# BarGraph.net
KiCad netlist of a schematic drawn in EAGLE
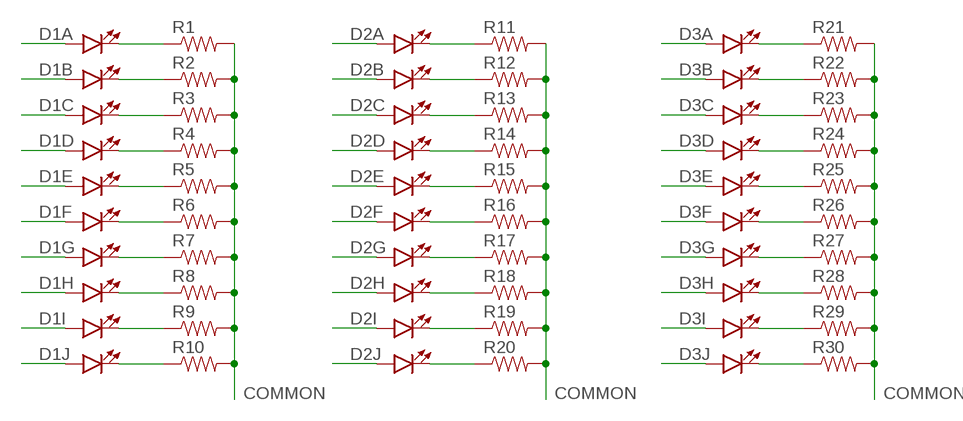
[diagram p0: schematic, sheet 1]

(export (version "E")
  (design (tool "Eeschema 10.0.6"))
  (components
    (comp (ref "D1")
      (value "LED_BARGRAPH_10")
      (footprint "eagle-import:LED_BARGAPH_10")
      (libsource (lib "eagle-import") (part "LED_BARGRAPH_10"))
    )
    (comp (ref "D2")
      (value "LED_BARGRAPH_10")
      (footprint "eagle-import:LED_BARGAPH_10")
      (libsource (lib "eagle-import") (part "LED_BARGRAPH_10"))
    )
    (comp (ref "D3")
      (value "LED_BARGRAPH_10")
      (footprint "eagle-import:LED_BARGAPH_10")
      (libsource (lib "eagle-import") (part "LED_BARGRAPH_10"))
    )
    (comp (ref "R1")
      (value "RESISTORPTH-1/4W")
      (footprint "eagle-import:AXIAL-0.4")
      (libsource (lib "eagle-import") (part "RESISTORPTH-1/4W"))
    )
    (comp (ref "R2")
      (value "RESISTORPTH-1/4W")
      (footprint "eagle-import:AXIAL-0.4")
      (libsource (lib "eagle-import") (part "RESISTORPTH-1/4W"))
    )
    (comp (ref "R3")
      (value "RESISTORPTH-1/4W")
      (footprint "eagle-import:AXIAL-0.4")
      (libsource (lib "eagle-import") (part "RESISTORPTH-1/4W"))
    )
    (comp (ref "R4")
      (value "RESISTORPTH-1/4W")
      (footprint "eagle-import:AXIAL-0.4")
      (libsource (lib "eagle-import") (part "RESISTORPTH-1/4W"))
    )
    (comp (ref "R5")
      (value "RESISTORPTH-1/4W")
      (footprint "eagle-import:AXIAL-0.4")
      (libsource (lib "eagle-import") (part "RESISTORPTH-1/4W"))
    )
    (comp (ref "R6")
      (value "RESISTORPTH-1/4W")
      (footprint "eagle-import:AXIAL-0.4")
      (libsource (lib "eagle-import") (part "RESISTORPTH-1/4W"))
    )
    (comp (ref "R7")
      (value "RESISTORPTH-1/4W")
      (footprint "eagle-import:AXIAL-0.4")
      (libsource (lib "eagle-import") (part "RESISTORPTH-1/4W"))
    )
    (comp (ref "R8")
      (value "RESISTORPTH-1/4W")
      (footprint "eagle-import:AXIAL-0.4")
      (libsource (lib "eagle-import") (part "RESISTORPTH-1/4W"))
    )
    (comp (ref "R9")
      (value "RESISTORPTH-1/4W")
      (footprint "eagle-import:AXIAL-0.4")
      (libsource (lib "eagle-import") (part "RESISTORPTH-1/4W"))
    )
    (comp (ref "R10")
      (value "RESISTORPTH-1/4W")
      (footprint "eagle-import:AXIAL-0.4")
      (libsource (lib "eagle-import") (part "RESISTORPTH-1/4W"))
    )
    (comp (ref "R11")
      (value "RESISTORPTH-1/4W")
      (footprint "eagle-import:AXIAL-0.4")
      (libsource (lib "eagle-import") (part "RESISTORPTH-1/4W"))
    )
    (comp (ref "R12")
      (value "RESISTORPTH-1/4W")
      (footprint "eagle-import:AXIAL-0.4")
      (libsource (lib "eagle-import") (part "RESISTORPTH-1/4W"))
    )
    (comp (ref "R13")
      (value "RESISTORPTH-1/4W")
      (footprint "eagle-import:AXIAL-0.4")
      (libsource (lib "eagle-import") (part "RESISTORPTH-1/4W"))
    )
    (comp (ref "R14")
      (value "RESISTORPTH-1/4W")
      (footprint "eagle-import:AXIAL-0.4")
      (libsource (lib "eagle-import") (part "RESISTORPTH-1/4W"))
    )
    (comp (ref "R15")
      (value "RESISTORPTH-1/4W")
      (footprint "eagle-import:AXIAL-0.4")
      (libsource (lib "eagle-import") (part "RESISTORPTH-1/4W"))
    )
    (comp (ref "R16")
      (value "RESISTORPTH-1/4W")
      (footprint "eagle-import:AXIAL-0.4")
      (libsource (lib "eagle-import") (part "RESISTORPTH-1/4W"))
    )
    (comp (ref "R17")
      (value "RESISTORPTH-1/4W")
      (footprint "eagle-import:AXIAL-0.4")
      (libsource (lib "eagle-import") (part "RESISTORPTH-1/4W"))
    )
    (comp (ref "R18")
      (value "RESISTORPTH-1/4W")
      (footprint "eagle-import:AXIAL-0.4")
      (libsource (lib "eagle-import") (part "RESISTORPTH-1/4W"))
    )
    (comp (ref "R19")
      (value "RESISTORPTH-1/4W")
      (footprint "eagle-import:AXIAL-0.4")
      (libsource (lib "eagle-import") (part "RESISTORPTH-1/4W"))
    )
    (comp (ref "R20")
      (value "RESISTORPTH-1/4W")
      (footprint "eagle-import:AXIAL-0.4")
      (libsource (lib "eagle-import") (part "RESISTORPTH-1/4W"))
    )
    (comp (ref "R21")
      (value "RESISTORPTH-1/4W")
      (footprint "eagle-import:AXIAL-0.4")
      (libsource (lib "eagle-import") (part "RESISTORPTH-1/4W"))
    )
    (comp (ref "R22")
      (value "RESISTORPTH-1/4W")
      (footprint "eagle-import:AXIAL-0.4")
      (libsource (lib "eagle-import") (part "RESISTORPTH-1/4W"))
    )
    (comp (ref "R23")
      (value "RESISTORPTH-1/4W")
      (footprint "eagle-import:AXIAL-0.4")
      (libsource (lib "eagle-import") (part "RESISTORPTH-1/4W"))
    )
    (comp (ref "R24")
      (value "RESISTORPTH-1/4W")
      (footprint "eagle-import:AXIAL-0.4")
      (libsource (lib "eagle-import") (part "RESISTORPTH-1/4W"))
    )
    (comp (ref "R25")
      (value "RESISTORPTH-1/4W")
      (footprint "eagle-import:AXIAL-0.4")
      (libsource (lib "eagle-import") (part "RESISTORPTH-1/4W"))
    )
    (comp (ref "R26")
      (value "RESISTORPTH-1/4W")
      (footprint "eagle-import:AXIAL-0.4")
      (libsource (lib "eagle-import") (part "RESISTORPTH-1/4W"))
    )
    (comp (ref "R27")
      (value "RESISTORPTH-1/4W")
      (footprint "eagle-import:AXIAL-0.4")
      (libsource (lib "eagle-import") (part "RESISTORPTH-1/4W"))
    )
    (comp (ref "R28")
      (value "RESISTORPTH-1/4W")
      (footprint "eagle-import:AXIAL-0.4")
      (libsource (lib "eagle-import") (part "RESISTORPTH-1/4W"))
    )
    (comp (ref "R29")
      (value "RESISTORPTH-1/4W")
      (footprint "eagle-import:AXIAL-0.4")
      (libsource (lib "eagle-import") (part "RESISTORPTH-1/4W"))
    )
    (comp (ref "R30")
      (value "RESISTORPTH-1/4W")
      (footprint "eagle-import:AXIAL-0.4")
      (libsource (lib "eagle-import") (part "RESISTORPTH-1/4W"))
    )
  )
  (nets
    (net (code "1") (name "/COMMON") (class "Default")
      (node (ref "R1") (pin "P$2") (pinfunction "2_P$2") (pintype "passive"))
      (node (ref "R10") (pin "P$2") (pinfunction "2_P$2") (pintype "passive"))
      (node (ref "R11") (pin "P$2") (pinfunction "2_P$2") (pintype "passive"))
      (node (ref "R12") (pin "P$2") (pinfunction "2_P$2") (pintype "passive"))
      (node (ref "R13") (pin "P$2") (pinfunction "2_P$2") (pintype "passive"))
      (node (ref "R14") (pin "P$2") (pinfunction "2_P$2") (pintype "passive"))
      (node (ref "R15") (pin "P$2") (pinfunction "2_P$2") (pintype "passive"))
      (node (ref "R16") (pin "P$2") (pinfunction "2_P$2") (pintype "passive"))
      (node (ref "R17") (pin "P$2") (pinfunction "2_P$2") (pintype "passive"))
      (node (ref "R18") (pin "P$2") (pinfunction "2_P$2") (pintype "passive"))
      (node (ref "R19") (pin "P$2") (pinfunction "2_P$2") (pintype "passive"))
      (node (ref "R2") (pin "P$2") (pinfunction "2_P$2") (pintype "passive"))
      (node (ref "R20") (pin "P$2") (pinfunction "2_P$2") (pintype "passive"))
      (node (ref "R21") (pin "P$2") (pinfunction "2_P$2") (pintype "passive"))
      (node (ref "R22") (pin "P$2") (pinfunction "2_P$2") (pintype "passive"))
      (node (ref "R23") (pin "P$2") (pinfunction "2_P$2") (pintype "passive"))
      (node (ref "R24") (pin "P$2") (pinfunction "2_P$2") (pintype "passive"))
      (node (ref "R25") (pin "P$2") (pinfunction "2_P$2") (pintype "passive"))
      (node (ref "R26") (pin "P$2") (pinfunction "2_P$2") (pintype "passive"))
      (node (ref "R27") (pin "P$2") (pinfunction "2_P$2") (pintype "passive"))
      (node (ref "R28") (pin "P$2") (pinfunction "2_P$2") (pintype "passive"))
      (node (ref "R29") (pin "P$2") (pinfunction "2_P$2") (pintype "passive"))
      (node (ref "R3") (pin "P$2") (pinfunction "2_P$2") (pintype "passive"))
      (node (ref "R30") (pin "P$2") (pinfunction "2_P$2") (pintype "passive"))
      (node (ref "R4") (pin "P$2") (pinfunction "2_P$2") (pintype "passive"))
      (node (ref "R5") (pin "P$2") (pinfunction "2_P$2") (pintype "passive"))
      (node (ref "R6") (pin "P$2") (pinfunction "2_P$2") (pintype "passive"))
      (node (ref "R7") (pin "P$2") (pinfunction "2_P$2") (pintype "passive"))
      (node (ref "R8") (pin "P$2") (pinfunction "2_P$2") (pintype "passive"))
      (node (ref "R9") (pin "P$2") (pinfunction "2_P$2") (pintype "passive"))
    )
    (net (code "2") (name "Net-(D1A-C)") (class "Default")
      (node (ref "D1") (pin "20") (pinfunction "C_20") (pintype "passive"))
      (node (ref "R1") (pin "P$1") (pinfunction "1_P$1") (pintype "passive"))
    )
    (net (code "3") (name "Net-(D1B-C)") (class "Default")
      (node (ref "D1") (pin "19") (pinfunction "C_19") (pintype "passive"))
      (node (ref "R2") (pin "P$1") (pinfunction "1_P$1") (pintype "passive"))
    )
    (net (code "4") (name "Net-(D1C-C)") (class "Default")
      (node (ref "D1") (pin "18") (pinfunction "C_18") (pintype "passive"))
      (node (ref "R3") (pin "P$1") (pinfunction "1_P$1") (pintype "passive"))
    )
    (net (code "5") (name "Net-(D1D-C)") (class "Default")
      (node (ref "D1") (pin "17") (pinfunction "C_17") (pintype "passive"))
      (node (ref "R4") (pin "P$1") (pinfunction "1_P$1") (pintype "passive"))
    )
    (net (code "6") (name "Net-(D1E-C)") (class "Default")
      (node (ref "D1") (pin "16") (pinfunction "C_16") (pintype "passive"))
      (node (ref "R5") (pin "P$1") (pinfunction "1_P$1") (pintype "passive"))
    )
    (net (code "7") (name "Net-(D1F-C)") (class "Default")
      (node (ref "D1") (pin "15") (pinfunction "C_15") (pintype "passive"))
      (node (ref "R6") (pin "P$1") (pinfunction "1_P$1") (pintype "passive"))
    )
    (net (code "8") (name "Net-(D1G-C)") (class "Default")
      (node (ref "D1") (pin "14") (pinfunction "C_14") (pintype "passive"))
      (node (ref "R7") (pin "P$1") (pinfunction "1_P$1") (pintype "passive"))
    )
    (net (code "9") (name "Net-(D1H-C)") (class "Default")
      (node (ref "D1") (pin "13") (pinfunction "C_13") (pintype "passive"))
      (node (ref "R8") (pin "P$1") (pinfunction "1_P$1") (pintype "passive"))
    )
    (net (code "10") (name "Net-(D1I-C)") (class "Default")
      (node (ref "D1") (pin "12") (pinfunction "C_12") (pintype "passive"))
      (node (ref "R9") (pin "P$1") (pinfunction "1_P$1") (pintype "passive"))
    )
    (net (code "11") (name "Net-(D1J-C)") (class "Default")
      (node (ref "D1") (pin "11") (pinfunction "C_11") (pintype "passive"))
      (node (ref "R10") (pin "P$1") (pinfunction "1_P$1") (pintype "passive"))
    )
    (net (code "12") (name "Net-(D2A-C)") (class "Default")
      (node (ref "D2") (pin "20") (pinfunction "C_20") (pintype "passive"))
      (node (ref "R11") (pin "P$1") (pinfunction "1_P$1") (pintype "passive"))
    )
    (net (code "13") (name "Net-(D2B-C)") (class "Default")
      (node (ref "D2") (pin "19") (pinfunction "C_19") (pintype "passive"))
      (node (ref "R12") (pin "P$1") (pinfunction "1_P$1") (pintype "passive"))
    )
    (net (code "14") (name "Net-(D2C-C)") (class "Default")
      (node (ref "D2") (pin "18") (pinfunction "C_18") (pintype "passive"))
      (node (ref "R13") (pin "P$1") (pinfunction "1_P$1") (pintype "passive"))
    )
    (net (code "15") (name "Net-(D2D-C)") (class "Default")
      (node (ref "D2") (pin "17") (pinfunction "C_17") (pintype "passive"))
      (node (ref "R14") (pin "P$1") (pinfunction "1_P$1") (pintype "passive"))
    )
    (net (code "16") (name "Net-(D2E-C)") (class "Default")
      (node (ref "D2") (pin "16") (pinfunction "C_16") (pintype "passive"))
      (node (ref "R15") (pin "P$1") (pinfunction "1_P$1") (pintype "passive"))
    )
    (net (code "17") (name "Net-(D2F-C)") (class "Default")
      (node (ref "D2") (pin "15") (pinfunction "C_15") (pintype "passive"))
      (node (ref "R16") (pin "P$1") (pinfunction "1_P$1") (pintype "passive"))
    )
    (net (code "18") (name "Net-(D2G-C)") (class "Default")
      (node (ref "D2") (pin "14") (pinfunction "C_14") (pintype "passive"))
      (node (ref "R17") (pin "P$1") (pinfunction "1_P$1") (pintype "passive"))
    )
    (net (code "19") (name "Net-(D2H-C)") (class "Default")
      (node (ref "D2") (pin "13") (pinfunction "C_13") (pintype "passive"))
      (node (ref "R18") (pin "P$1") (pinfunction "1_P$1") (pintype "passive"))
    )
    (net (code "20") (name "Net-(D2I-C)") (class "Default")
      (node (ref "D2") (pin "12") (pinfunction "C_12") (pintype "passive"))
      (node (ref "R19") (pin "P$1") (pinfunction "1_P$1") (pintype "passive"))
    )
    (net (code "21") (name "Net-(D2J-C)") (class "Default")
      (node (ref "D2") (pin "11") (pinfunction "C_11") (pintype "passive"))
      (node (ref "R20") (pin "P$1") (pinfunction "1_P$1") (pintype "passive"))
    )
    (net (code "22") (name "Net-(D3A-C)") (class "Default")
      (node (ref "D3") (pin "20") (pinfunction "C_20") (pintype "passive"))
      (node (ref "R21") (pin "P$1") (pinfunction "1_P$1") (pintype "passive"))
    )
    (net (code "23") (name "Net-(D3B-C)") (class "Default")
      (node (ref "D3") (pin "19") (pinfunction "C_19") (pintype "passive"))
      (node (ref "R22") (pin "P$1") (pinfunction "1_P$1") (pintype "passive"))
    )
    (net (code "24") (name "Net-(D3C-C)") (class "Default")
      (node (ref "D3") (pin "18") (pinfunction "C_18") (pintype "passive"))
      (node (ref "R23") (pin "P$1") (pinfunction "1_P$1") (pintype "passive"))
    )
    (net (code "25") (name "Net-(D3D-C)") (class "Default")
      (node (ref "D3") (pin "17") (pinfunction "C_17") (pintype "passive"))
      (node (ref "R24") (pin "P$1") (pinfunction "1_P$1") (pintype "passive"))
    )
    (net (code "26") (name "Net-(D3E-C)") (class "Default")
      (node (ref "D3") (pin "16") (pinfunction "C_16") (pintype "passive"))
      (node (ref "R25") (pin "P$1") (pinfunction "1_P$1") (pintype "passive"))
    )
    (net (code "27") (name "Net-(D3F-C)") (class "Default")
      (node (ref "D3") (pin "15") (pinfunction "C_15") (pintype "passive"))
      (node (ref "R26") (pin "P$1") (pinfunction "1_P$1") (pintype "passive"))
    )
    (net (code "28") (name "Net-(D3G-C)") (class "Default")
      (node (ref "D3") (pin "14") (pinfunction "C_14") (pintype "passive"))
      (node (ref "R27") (pin "P$1") (pinfunction "1_P$1") (pintype "passive"))
    )
    (net (code "29") (name "Net-(D3H-C)") (class "Default")
      (node (ref "D3") (pin "13") (pinfunction "C_13") (pintype "passive"))
      (node (ref "R28") (pin "P$1") (pinfunction "1_P$1") (pintype "passive"))
    )
    (net (code "30") (name "Net-(D3I-C)") (class "Default")
      (node (ref "D3") (pin "12") (pinfunction "C_12") (pintype "passive"))
      (node (ref "R29") (pin "P$1") (pinfunction "1_P$1") (pintype "passive"))
    )
    (net (code "31") (name "Net-(D3J-C)") (class "Default")
      (node (ref "D3") (pin "11") (pinfunction "C_11") (pintype "passive"))
      (node (ref "R30") (pin "P$1") (pinfunction "1_P$1") (pintype "passive"))
    )
    (net (code "32") (name "unconnected-(D1A-A-Pad1)") (class "Default")
      (node (ref "D1") (pin "1") (pinfunction "A_1") (pintype "passive"))
    )
    (net (code "33") (name "unconnected-(D1B-A-Pad2)") (class "Default")
      (node (ref "D1") (pin "2") (pinfunction "A_2") (pintype "passive"))
    )
    (net (code "34") (name "unconnected-(D1C-A-Pad3)") (class "Default")
      (node (ref "D1") (pin "3") (pinfunction "A_3") (pintype "passive"))
    )
    (net (code "35") (name "unconnected-(D1D-A-Pad4)") (class "Default")
      (node (ref "D1") (pin "4") (pinfunction "A_4") (pintype "passive"))
    )
    (net (code "36") (name "unconnected-(D1E-A-Pad5)") (class "Default")
      (node (ref "D1") (pin "5") (pinfunction "A_5") (pintype "passive"))
    )
    (net (code "37") (name "unconnected-(D1F-A-Pad6)") (class "Default")
      (node (ref "D1") (pin "6") (pinfunction "A_6") (pintype "passive"))
    )
    (net (code "38") (name "unconnected-(D1G-A-Pad7)") (class "Default")
      (node (ref "D1") (pin "7") (pinfunction "A_7") (pintype "passive"))
    )
    (net (code "39") (name "unconnected-(D1H-A-Pad8)") (class "Default")
      (node (ref "D1") (pin "8") (pinfunction "A_8") (pintype "passive"))
    )
    (net (code "40") (name "unconnected-(D1I-A-Pad9)") (class "Default")
      (node (ref "D1") (pin "9") (pinfunction "A_9") (pintype "passive"))
    )
    (net (code "41") (name "unconnected-(D1J-A-Pad10)") (class "Default")
      (node (ref "D1") (pin "10") (pinfunction "A_10") (pintype "passive"))
    )
    (net (code "42") (name "unconnected-(D2A-A-Pad1)") (class "Default")
      (node (ref "D2") (pin "1") (pinfunction "A_1") (pintype "passive"))
    )
    (net (code "43") (name "unconnected-(D2B-A-Pad2)") (class "Default")
      (node (ref "D2") (pin "2") (pinfunction "A_2") (pintype "passive"))
    )
    (net (code "44") (name "unconnected-(D2C-A-Pad3)") (class "Default")
      (node (ref "D2") (pin "3") (pinfunction "A_3") (pintype "passive"))
    )
    (net (code "45") (name "unconnected-(D2D-A-Pad4)") (class "Default")
      (node (ref "D2") (pin "4") (pinfunction "A_4") (pintype "passive"))
    )
    (net (code "46") (name "unconnected-(D2E-A-Pad5)") (class "Default")
      (node (ref "D2") (pin "5") (pinfunction "A_5") (pintype "passive"))
    )
    (net (code "47") (name "unconnected-(D2F-A-Pad6)") (class "Default")
      (node (ref "D2") (pin "6") (pinfunction "A_6") (pintype "passive"))
    )
    (net (code "48") (name "unconnected-(D2G-A-Pad7)") (class "Default")
      (node (ref "D2") (pin "7") (pinfunction "A_7") (pintype "passive"))
    )
    (net (code "49") (name "unconnected-(D2H-A-Pad8)") (class "Default")
      (node (ref "D2") (pin "8") (pinfunction "A_8") (pintype "passive"))
    )
    (net (code "50") (name "unconnected-(D2I-A-Pad9)") (class "Default")
      (node (ref "D2") (pin "9") (pinfunction "A_9") (pintype "passive"))
    )
    (net (code "51") (name "unconnected-(D2J-A-Pad10)") (class "Default")
      (node (ref "D2") (pin "10") (pinfunction "A_10") (pintype "passive"))
    )
    (net (code "52") (name "unconnected-(D3A-A-Pad1)") (class "Default")
      (node (ref "D3") (pin "1") (pinfunction "A_1") (pintype "passive"))
    )
    (net (code "53") (name "unconnected-(D3B-A-Pad2)") (class "Default")
      (node (ref "D3") (pin "2") (pinfunction "A_2") (pintype "passive"))
    )
    (net (code "54") (name "unconnected-(D3C-A-Pad3)") (class "Default")
      (node (ref "D3") (pin "3") (pinfunction "A_3") (pintype "passive"))
    )
    (net (code "55") (name "unconnected-(D3D-A-Pad4)") (class "Default")
      (node (ref "D3") (pin "4") (pinfunction "A_4") (pintype "passive"))
    )
    (net (code "56") (name "unconnected-(D3E-A-Pad5)") (class "Default")
      (node (ref "D3") (pin "5") (pinfunction "A_5") (pintype "passive"))
    )
    (net (code "57") (name "unconnected-(D3F-A-Pad6)") (class "Default")
      (node (ref "D3") (pin "6") (pinfunction "A_6") (pintype "passive"))
    )
    (net (code "58") (name "unconnected-(D3G-A-Pad7)") (class "Default")
      (node (ref "D3") (pin "7") (pinfunction "A_7") (pintype "passive"))
    )
    (net (code "59") (name "unconnected-(D3H-A-Pad8)") (class "Default")
      (node (ref "D3") (pin "8") (pinfunction "A_8") (pintype "passive"))
    )
    (net (code "60") (name "unconnected-(D3I-A-Pad9)") (class "Default")
      (node (ref "D3") (pin "9") (pinfunction "A_9") (pintype "passive"))
    )
    (net (code "61") (name "unconnected-(D3J-A-Pad10)") (class "Default")
      (node (ref "D3") (pin "10") (pinfunction "A_10") (pintype "passive"))
    )
  )
)
